# SL1_Xilinx_Spartan-IIE_PQ208_Rev1_02.net
KiCad netlist of a schematic drawn in Altium Designer
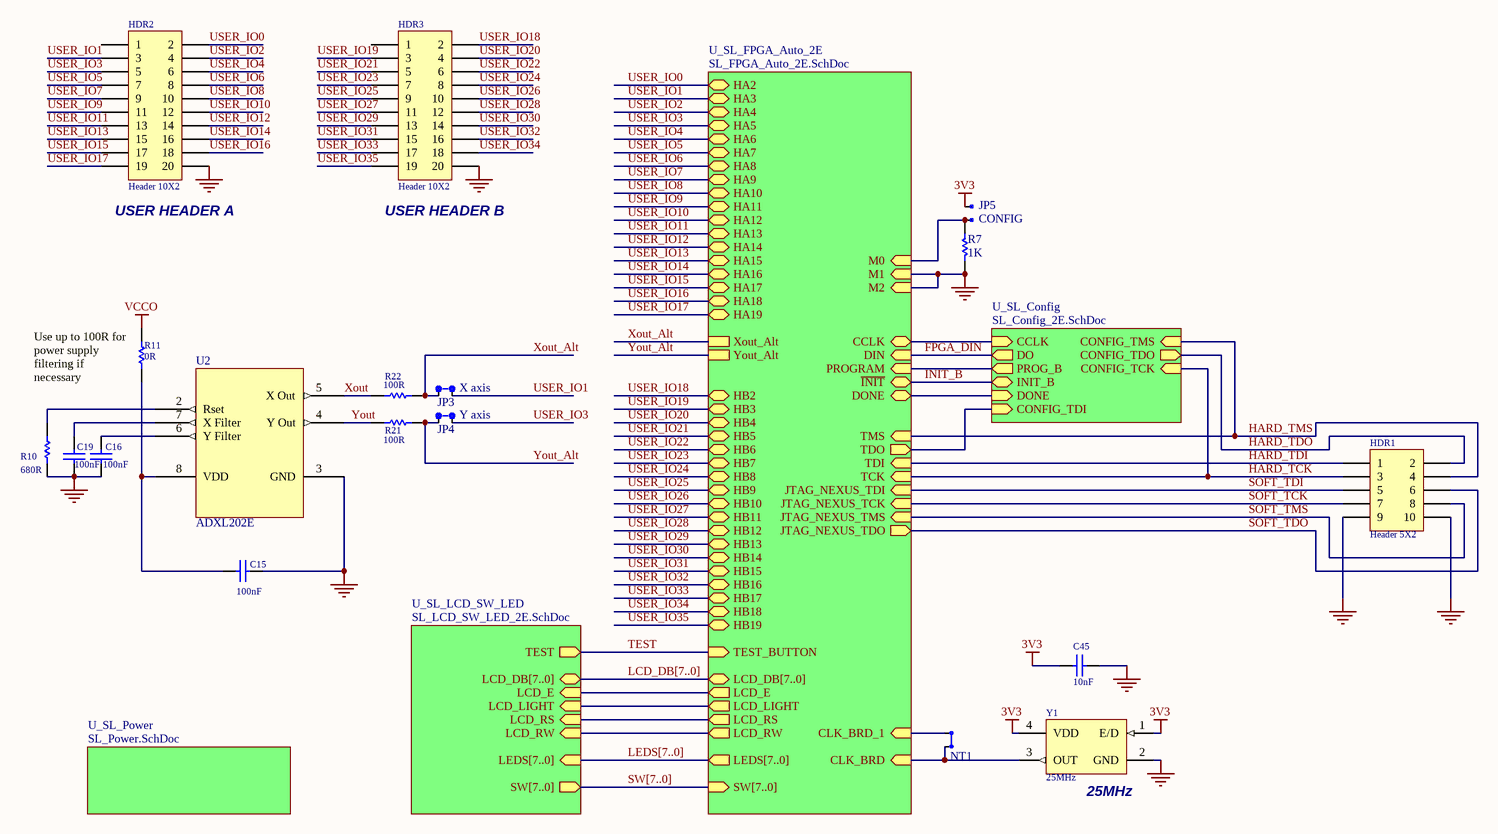
[diagram p0:  SL1 Xilinx Spartan-IIE PQ208 Rev1.02.SchDoc]

(export (version "E")
  (design (tool "Eeschema 10.0.6"))
  (components
    (comp (ref "C15")
      (value "100nF")
      (footprint "CC1608-0603")
      (description "Capacitor")
      (libsource (lib "SpiritLevel_2E") (part "CAP"))
    )
    (comp (ref "C16")
      (value "100nF")
      (footprint "CC1608-0603")
      (description "Capacitor")
      (libsource (lib "SpiritLevel_2E") (part "CAP"))
    )
    (comp (ref "C19")
      (value "100nF")
      (footprint "CC1608-0603")
      (description "Capacitor")
      (libsource (lib "SpiritLevel_2E") (part "CAP"))
    )
    (comp (ref "C45")
      (value "10nF")
      (footprint "CC1608-0603")
      (description "Capacitor")
      (libsource (lib "SpiritLevel_2E") (part "CAP"))
    )
    (comp (ref "HDR1")
      (value "Header 5X2")
      (footprint "Spirit_Level_Project:HDR2X5_LP")
      (description "Header, 5-Pin, Dual row")
      (libsource (lib "SpiritLevel_2E") (part "Header 5X2"))
    )
    (comp (ref "HDR2")
      (value "Header 10X2")
      (footprint "Spirit_Level_Project:HDR2X10")
      (description "Header, 10-Pin, Dual row")
      (libsource (lib "SpiritLevel_2E") (part "Header 10X2"))
    )
    (comp (ref "HDR3")
      (value "Header 10X2")
      (footprint "Spirit_Level_Project:HDR2X10")
      (description "Header, 10-Pin, Dual row")
      (libsource (lib "SpiritLevel_2E") (part "Header 10X2"))
    )
    (comp (ref "JP3")
      (value "X axis")
      (footprint "Spirit_Level_Project:HDR1X2")
      (description "Jumper, 2-Pin")
      (libsource (lib "SpiritLevel_2E") (part "Jumper, 2-Pin"))
    )
    (comp (ref "JP4")
      (value "Y axis")
      (footprint "Spirit_Level_Project:HDR1X2")
      (description "Jumper, 2-Pin")
      (libsource (lib "SpiritLevel_2E") (part "Jumper, 2-Pin"))
    )
    (comp (ref "JP5")
      (value "CONFIG")
      (footprint "Spirit_Level_Project:HDR1X2")
      (description "Jumper, 2-Pin")
      (libsource (lib "SpiritLevel_2E") (part "Jumper, 2-Pin"))
    )
    (comp (ref "JS2")
      (value "Short Linking")
      (description "Shorting Link, 2.54mm (0.1\") Pitch")
      (libsource (lib "SpiritLevel_2E") (part "Jumper Socket"))
    )
    (comp (ref "JS3")
      (value "Shorting Link")
      (description "Shorting Link, 2.54mm (0.1\") Pitch")
      (libsource (lib "SpiritLevel_2E") (part "Jumper Socket"))
    )
    (comp (ref "NT1")
      (value "GND")
      (footprint "Spirit_Level_Project:NT")
      (description "Jumper, 2-Pin")
      (libsource (lib "SpiritLevel_2E") (part "Jumper, 2-Pin_1"))
    )
    (comp (ref "R7")
      (value "1K")
      (footprint "Spirit_Level_Project:CR2012-0805")
      (description "Resistor")
      (libsource (lib "SpiritLevel_2E") (part "RES"))
    )
    (comp (ref "R10")
      (value "680R")
      (footprint "Spirit_Level_Project:CR2012-0805")
      (description "Resistor")
      (libsource (lib "SpiritLevel_2E") (part "Res1"))
    )
    (comp (ref "R11")
      (value "0R")
      (footprint "Spirit_Level_Project:CR2012-0805")
      (description "Resistor")
      (libsource (lib "SpiritLevel_2E") (part "RES"))
    )
    (comp (ref "R21")
      (value "100R")
      (footprint "Spirit_Level_Project:CR2012-0805")
      (description "Resistor")
      (libsource (lib "SpiritLevel_2E") (part "Res1"))
    )
    (comp (ref "R22")
      (value "100R")
      (footprint "Spirit_Level_Project:CR2012-0805")
      (description "Resistor")
      (libsource (lib "SpiritLevel_2E") (part "Res1"))
    )
    (comp (ref "U2")
      (value "ADXL202E")
      (footprint "Spirit_Level_Project:E-8")
      (description "Accelerometer with Digital Output")
      (libsource (lib "SpiritLevel_2E") (part "ADXL202E"))
    )
    (comp (ref "Y1")
      (value "25MHz")
      (footprint "Spirit_Level_Project:QSMO_4200")
      (description "Surface Mount Crystal Oscillator")
      (libsource (lib "SpiritLevel_2E") (part "QSMO_4200"))
    )
  )
  (nets
    (net (code "26") (name "/CLK_BRD") (class "Default")
      (node (ref "NT1") (pin "2") (pinfunction "2_2") (pintype "passive"))
      (node (ref "Y1") (pin "3") (pinfunction "OUT_3") (pintype "output"))
    )
    (net (code "27") (name "/CLK_BRD_1") (class "Default")
      (node (ref "NT1") (pin "1") (pinfunction "1_1") (pintype "passive"))
    )
    (net (code "30") (name "/HARD_TCK") (class "Default")
      (node (ref "HDR1") (pin "3") (pinfunction "3_3") (pintype "passive"))
    )
    (net (code "31") (name "/HARD_TDI") (class "Default")
      (node (ref "HDR1") (pin "1") (pinfunction "1_1") (pintype "passive"))
    )
    (net (code "32") (name "/HARD_TDO") (class "Default")
      (node (ref "HDR1") (pin "2") (pinfunction "2_2") (pintype "passive"))
    )
    (net (code "33") (name "/HARD_TMS") (class "Default")
      (node (ref "HDR1") (pin "4") (pinfunction "4_4") (pintype "passive"))
    )
    (net (code "41") (name "/M0") (class "Default")
      (node (ref "JP5") (pin "1") (pinfunction "1_1") (pintype "passive"))
      (node (ref "R7") (pin "2") (pinfunction "2_2") (pintype "passive"))
    )
    (net (code "43") (name "/SOFT_TCK") (class "Default")
      (node (ref "HDR1") (pin "7") (pinfunction "7_7") (pintype "passive"))
    )
    (net (code "44") (name "/SOFT_TDI") (class "Default")
      (node (ref "HDR1") (pin "5") (pinfunction "5_5") (pintype "passive"))
    )
    (net (code "45") (name "/SOFT_TDO") (class "Default")
      (node (ref "HDR1") (pin "6") (pinfunction "6_6") (pintype "passive"))
    )
    (net (code "46") (name "/SOFT_TMS") (class "Default")
      (node (ref "HDR1") (pin "8") (pinfunction "8_8") (pintype "passive"))
    )
    (net (code "50") (name "/USER_IO0") (class "Default")
      (node (ref "HDR2") (pin "2") (pinfunction "2_2") (pintype "passive"))
    )
    (net (code "51") (name "/USER_IO1") (class "Default")
      (node (ref "HDR2") (pin "3") (pinfunction "3_3") (pintype "passive"))
      (node (ref "JP3") (pin "2") (pinfunction "2_2") (pintype "passive"))
    )
    (net (code "52") (name "/USER_IO2") (class "Default")
      (node (ref "HDR2") (pin "4") (pinfunction "4_4") (pintype "passive"))
    )
    (net (code "53") (name "/USER_IO3") (class "Default")
      (node (ref "HDR2") (pin "5") (pinfunction "5_5") (pintype "passive"))
      (node (ref "JP4") (pin "2") (pinfunction "2_2") (pintype "passive"))
    )
    (net (code "54") (name "/USER_IO4") (class "Default")
      (node (ref "HDR2") (pin "6") (pinfunction "6_6") (pintype "passive"))
    )
    (net (code "55") (name "/USER_IO5") (class "Default")
      (node (ref "HDR2") (pin "7") (pinfunction "7_7") (pintype "passive"))
    )
    (net (code "56") (name "/USER_IO6") (class "Default")
      (node (ref "HDR2") (pin "8") (pinfunction "8_8") (pintype "passive"))
    )
    (net (code "57") (name "/USER_IO7") (class "Default")
      (node (ref "HDR2") (pin "9") (pinfunction "9_9") (pintype "passive"))
    )
    (net (code "58") (name "/USER_IO8") (class "Default")
      (node (ref "HDR2") (pin "10") (pinfunction "10_10") (pintype "passive"))
    )
    (net (code "59") (name "/USER_IO9") (class "Default")
      (node (ref "HDR2") (pin "11") (pinfunction "11_11") (pintype "passive"))
    )
    (net (code "60") (name "/USER_IO10") (class "Default")
      (node (ref "HDR2") (pin "12") (pinfunction "12_12") (pintype "passive"))
    )
    (net (code "61") (name "/USER_IO11") (class "Default")
      (node (ref "HDR2") (pin "13") (pinfunction "13_13") (pintype "passive"))
    )
    (net (code "62") (name "/USER_IO12") (class "Default")
      (node (ref "HDR2") (pin "14") (pinfunction "14_14") (pintype "passive"))
    )
    (net (code "63") (name "/USER_IO13") (class "Default")
      (node (ref "HDR2") (pin "15") (pinfunction "15_15") (pintype "passive"))
    )
    (net (code "64") (name "/USER_IO14") (class "Default")
      (node (ref "HDR2") (pin "16") (pinfunction "16_16") (pintype "passive"))
    )
    (net (code "65") (name "/USER_IO15") (class "Default")
      (node (ref "HDR2") (pin "17") (pinfunction "17_17") (pintype "passive"))
    )
    (net (code "66") (name "/USER_IO16") (class "Default")
      (node (ref "HDR2") (pin "18") (pinfunction "18_18") (pintype "passive"))
    )
    (net (code "67") (name "/USER_IO17") (class "Default")
      (node (ref "HDR2") (pin "19") (pinfunction "19_19") (pintype "passive"))
    )
    (net (code "68") (name "/USER_IO18") (class "Default")
      (node (ref "HDR3") (pin "2") (pinfunction "2_2") (pintype "passive"))
    )
    (net (code "69") (name "/USER_IO19") (class "Default")
      (node (ref "HDR3") (pin "3") (pinfunction "3_3") (pintype "passive"))
    )
    (net (code "70") (name "/USER_IO20") (class "Default")
      (node (ref "HDR3") (pin "4") (pinfunction "4_4") (pintype "passive"))
    )
    (net (code "71") (name "/USER_IO21") (class "Default")
      (node (ref "HDR3") (pin "5") (pinfunction "5_5") (pintype "passive"))
    )
    (net (code "72") (name "/USER_IO22") (class "Default")
      (node (ref "HDR3") (pin "6") (pinfunction "6_6") (pintype "passive"))
    )
    (net (code "73") (name "/USER_IO23") (class "Default")
      (node (ref "HDR3") (pin "7") (pinfunction "7_7") (pintype "passive"))
    )
    (net (code "74") (name "/USER_IO24") (class "Default")
      (node (ref "HDR3") (pin "8") (pinfunction "8_8") (pintype "passive"))
    )
    (net (code "75") (name "/USER_IO25") (class "Default")
      (node (ref "HDR3") (pin "9") (pinfunction "9_9") (pintype "passive"))
    )
    (net (code "76") (name "/USER_IO26") (class "Default")
      (node (ref "HDR3") (pin "10") (pinfunction "10_10") (pintype "passive"))
    )
    (net (code "77") (name "/USER_IO27") (class "Default")
      (node (ref "HDR3") (pin "11") (pinfunction "11_11") (pintype "passive"))
    )
    (net (code "78") (name "/USER_IO28") (class "Default")
      (node (ref "HDR3") (pin "12") (pinfunction "12_12") (pintype "passive"))
    )
    (net (code "79") (name "/USER_IO29") (class "Default")
      (node (ref "HDR3") (pin "13") (pinfunction "13_13") (pintype "passive"))
    )
    (net (code "80") (name "/USER_IO30") (class "Default")
      (node (ref "HDR3") (pin "14") (pinfunction "14_14") (pintype "passive"))
    )
    (net (code "81") (name "/USER_IO31") (class "Default")
      (node (ref "HDR3") (pin "15") (pinfunction "15_15") (pintype "passive"))
    )
    (net (code "82") (name "/USER_IO32") (class "Default")
      (node (ref "HDR3") (pin "16") (pinfunction "16_16") (pintype "passive"))
    )
    (net (code "83") (name "/USER_IO33") (class "Default")
      (node (ref "HDR3") (pin "17") (pinfunction "17_17") (pintype "passive"))
    )
    (net (code "84") (name "/USER_IO34") (class "Default")
      (node (ref "HDR3") (pin "18") (pinfunction "18_18") (pintype "passive"))
    )
    (net (code "85") (name "/USER_IO35") (class "Default")
      (node (ref "HDR3") (pin "19") (pinfunction "19_19") (pintype "passive"))
    )
    (net (code "86") (name "/Xout") (class "Default")
      (node (ref "R22") (pin "2") (pinfunction "2_2") (pintype "passive"))
      (node (ref "U2") (pin "5") (pinfunction "X_Out_5") (pintype "output"))
    )
    (net (code "87") (name "/Xout_Alt") (class "Default")
      (node (ref "JP3") (pin "1") (pinfunction "1_1") (pintype "passive"))
      (node (ref "R22") (pin "1") (pinfunction "1_1") (pintype "passive"))
    )
    (net (code "88") (name "/Yout") (class "Default")
      (node (ref "R21") (pin "2") (pinfunction "2_2") (pintype "passive"))
      (node (ref "U2") (pin "4") (pinfunction "Y_Out_4") (pintype "output"))
    )
    (net (code "89") (name "/Yout_Alt") (class "Default")
      (node (ref "JP4") (pin "1") (pinfunction "1_1") (pintype "passive"))
      (node (ref "R21") (pin "1") (pinfunction "1_1") (pintype "passive"))
    )
    (net (code "90") (name "3V3") (class "Default")
      (node (ref "C45") (pin "1") (pinfunction "1_1") (pintype "passive"))
      (node (ref "JP5") (pin "2") (pinfunction "2_2") (pintype "passive"))
      (node (ref "Y1") (pin "1") (pinfunction "E/D_1") (pintype "input"))
      (node (ref "Y1") (pin "4") (pinfunction "VDD_4") (pintype "power_in"))
    )
    (net (code "91") (name "GND") (class "Default")
      (node (ref "C15") (pin "2") (pinfunction "2_2") (pintype "passive"))
      (node (ref "C16") (pin "2") (pinfunction "2_2") (pintype "passive"))
      (node (ref "C19") (pin "2") (pinfunction "2_2") (pintype "passive"))
      (node (ref "C45") (pin "2") (pinfunction "2_2") (pintype "passive"))
      (node (ref "HDR1") (pin "10") (pinfunction "10_10") (pintype "passive"))
      (node (ref "HDR1") (pin "9") (pinfunction "9_9") (pintype "passive"))
      (node (ref "HDR2") (pin "20") (pinfunction "20_20") (pintype "passive"))
      (node (ref "HDR3") (pin "20") (pinfunction "20_20") (pintype "passive"))
      (node (ref "R10") (pin "1") (pinfunction "1_1") (pintype "passive"))
      (node (ref "R7") (pin "1") (pinfunction "1_1") (pintype "passive"))
      (node (ref "U2") (pin "3") (pinfunction "GND_3") (pintype "power_in"))
      (node (ref "Y1") (pin "2") (pinfunction "GND_2") (pintype "power_in"))
    )
    (net (code "92") (name "Net-(U2-Rset)") (class "Default")
      (node (ref "R10") (pin "2") (pinfunction "2_2") (pintype "passive"))
      (node (ref "U2") (pin "2") (pinfunction "Rset_2") (pintype "output"))
    )
    (net (code "93") (name "Net-(U2-VDD)") (class "Default")
      (node (ref "C15") (pin "1") (pinfunction "1_1") (pintype "passive"))
      (node (ref "R11") (pin "2") (pinfunction "2_2") (pintype "passive"))
      (node (ref "U2") (pin "8") (pinfunction "VDD_8") (pintype "power_in"))
    )
    (net (code "94") (name "Net-(U2-X_Filter)") (class "Default")
      (node (ref "C19") (pin "1") (pinfunction "1_1") (pintype "passive"))
      (node (ref "U2") (pin "7") (pinfunction "X_Filter_7") (pintype "output"))
    )
    (net (code "95") (name "Net-(U2-Y_Filter)") (class "Default")
      (node (ref "C16") (pin "1") (pinfunction "1_1") (pintype "passive"))
      (node (ref "U2") (pin "6") (pinfunction "Y_Filter_6") (pintype "output"))
    )
    (net (code "96") (name "VCCO") (class "Default")
      (node (ref "R11") (pin "1") (pinfunction "1_1") (pintype "passive"))
    )
    (net (code "97") (name "unconnected-(HDR2-Pad1)") (class "Default")
      (node (ref "HDR2") (pin "1") (pinfunction "1_1") (pintype "passive"))
    )
    (net (code "98") (name "unconnected-(HDR3-Pad1)") (class "Default")
      (node (ref "HDR3") (pin "1") (pinfunction "1_1") (pintype "passive"))
    )
    (net (code "99") (name "unconnected-(U2-Self_Test-Pad1)") (class "Default")
      (node (ref "U2") (pin "1") (pinfunction "Self_Test_1") (pintype "input"))
    )
  )
)
